# SCH_personalCard_2024-08-03.net
KiCad netlist of a schematic drawn in EasyEDA
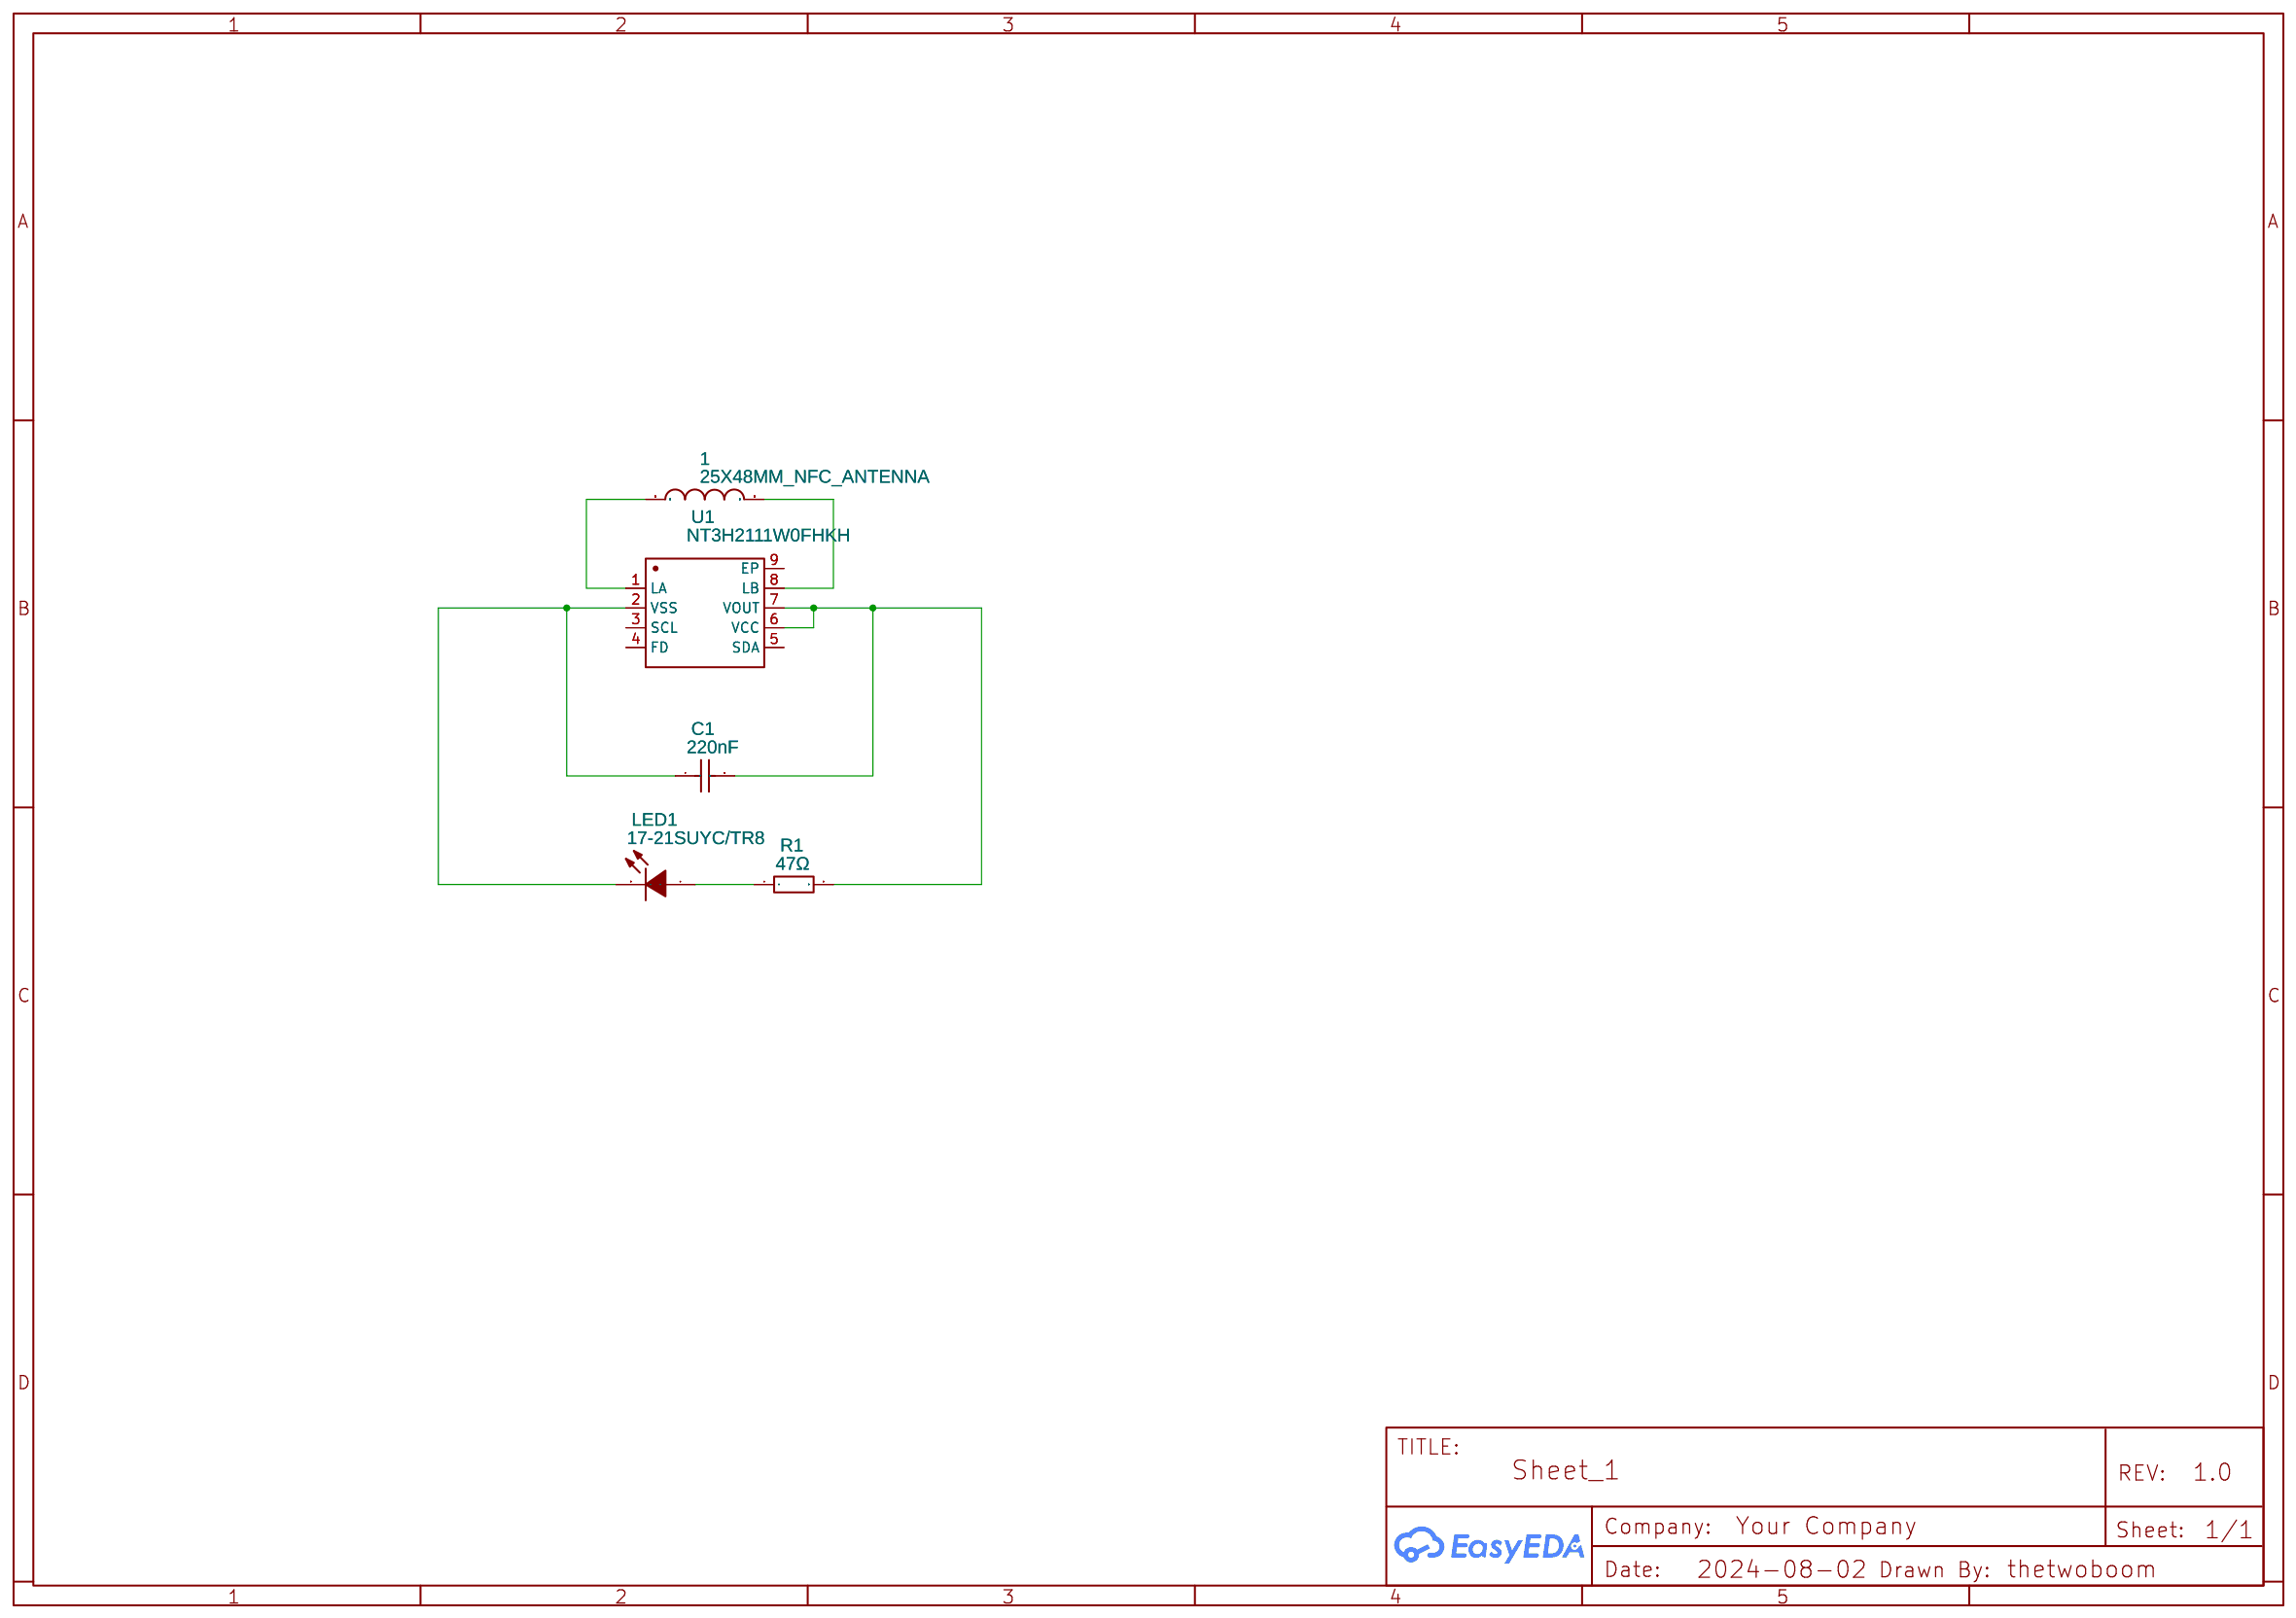
[diagram p0: schematic sheet]

(export (version "E")
  (design (tool "Eeschema 10.0.6"))
  (components
    (comp (ref "1") (value "25X48MM_NFC_ANTENNA") (libsource (lib "") (part "25X48MM_NFC_ANTENNA")))
    (comp (ref "C1")
      (value "220nF")
      (fields
        (field (name "Manufacturer Part") "CL10B224KA8NNNC")
        (field (name "Manufacturer") "SAMSUNG(三星)")
      )
      (libsource (lib "") (part "CL10B224KA8NNNC"))
    )
    (comp (ref "LED1")
      (value "17-21SUYC/TR8")
      (fields (field (name "Manufacturer Part") "KT-0805黄灯") (field (name "Manufacturer") "KENTO"))
      (libsource (lib "") (part "17-21SUYC/TR8"))
    )
    (comp (ref "R1")
      (value "47Ω")
      (fields
        (field (name "Manufacturer Part") "0603WAF470JT5E")
        (field (name "Manufacturer") "UNI-ROYAL(厚声)")
      )
      (libsource (lib "") (part "0603WAF470JT5E"))
    )
    (comp (ref "U1")
      (value "NT3H2111W0FHKH")
      (fields (field (name "Manufacturer") "NXP(恩智浦)"))
      (libsource (lib "") (part "NT3H2111W0FHKH"))
    )
  )
  (nets
    (net (code "1") (name "Net-(LED1-+)") (class "Default")
      (node (ref "LED1") (pin "1") (pinfunction "+_1") (pintype "unspecified"))
      (node (ref "R1") (pin "1") (pinfunction "1_1") (pintype "input"))
    )
    (net (code "2") (name "Net-(LED1--)") (class "Default")
      (node (ref "C1") (pin "1") (pinfunction "1_1") (pintype "input"))
      (node (ref "LED1") (pin "2") (pinfunction "-_2") (pintype "unspecified"))
      (node (ref "U1") (pin "2") (pinfunction "VSS_2") (pintype "unspecified"))
    )
    (net (code "3") (name "Net-(U1-LA)") (class "Default")
      (node (ref "1") (pin "P$1") (pinfunction "P$1_P$1") (pintype "bidirectional"))
      (node (ref "U1") (pin "1") (pinfunction "LA_1") (pintype "unspecified"))
    )
    (net (code "4") (name "Net-(U1-LB)") (class "Default")
      (node (ref "1") (pin "P$2") (pinfunction "P$2_P$2") (pintype "bidirectional"))
      (node (ref "U1") (pin "8") (pinfunction "LB_8") (pintype "unspecified"))
    )
    (net (code "5") (name "Net-(U1-VCC)") (class "Default")
      (node (ref "C1") (pin "2") (pinfunction "2_2") (pintype "input"))
      (node (ref "R1") (pin "2") (pinfunction "2_2") (pintype "input"))
      (node (ref "U1") (pin "6") (pinfunction "VCC_6") (pintype "unspecified"))
      (node (ref "U1") (pin "7") (pinfunction "VOUT_7") (pintype "unspecified"))
    )
    (net (code "6") (name "unconnected-(U1-EP-Pad9)") (class "Default")
      (node (ref "U1") (pin "9") (pinfunction "EP_9") (pintype "unspecified"))
    )
    (net (code "7") (name "unconnected-(U1-FD-Pad4)") (class "Default")
      (node (ref "U1") (pin "4") (pinfunction "FD_4") (pintype "unspecified"))
    )
    (net (code "8") (name "unconnected-(U1-SCL-Pad3)") (class "Default")
      (node (ref "U1") (pin "3") (pinfunction "SCL_3") (pintype "unspecified"))
    )
    (net (code "9") (name "unconnected-(U1-SDA-Pad5)") (class "Default")
      (node (ref "U1") (pin "5") (pinfunction "SDA_5") (pintype "unspecified"))
    )
  )
)
